# Sheet3.net
KiCad netlist of a schematic drawn in Altium Designer
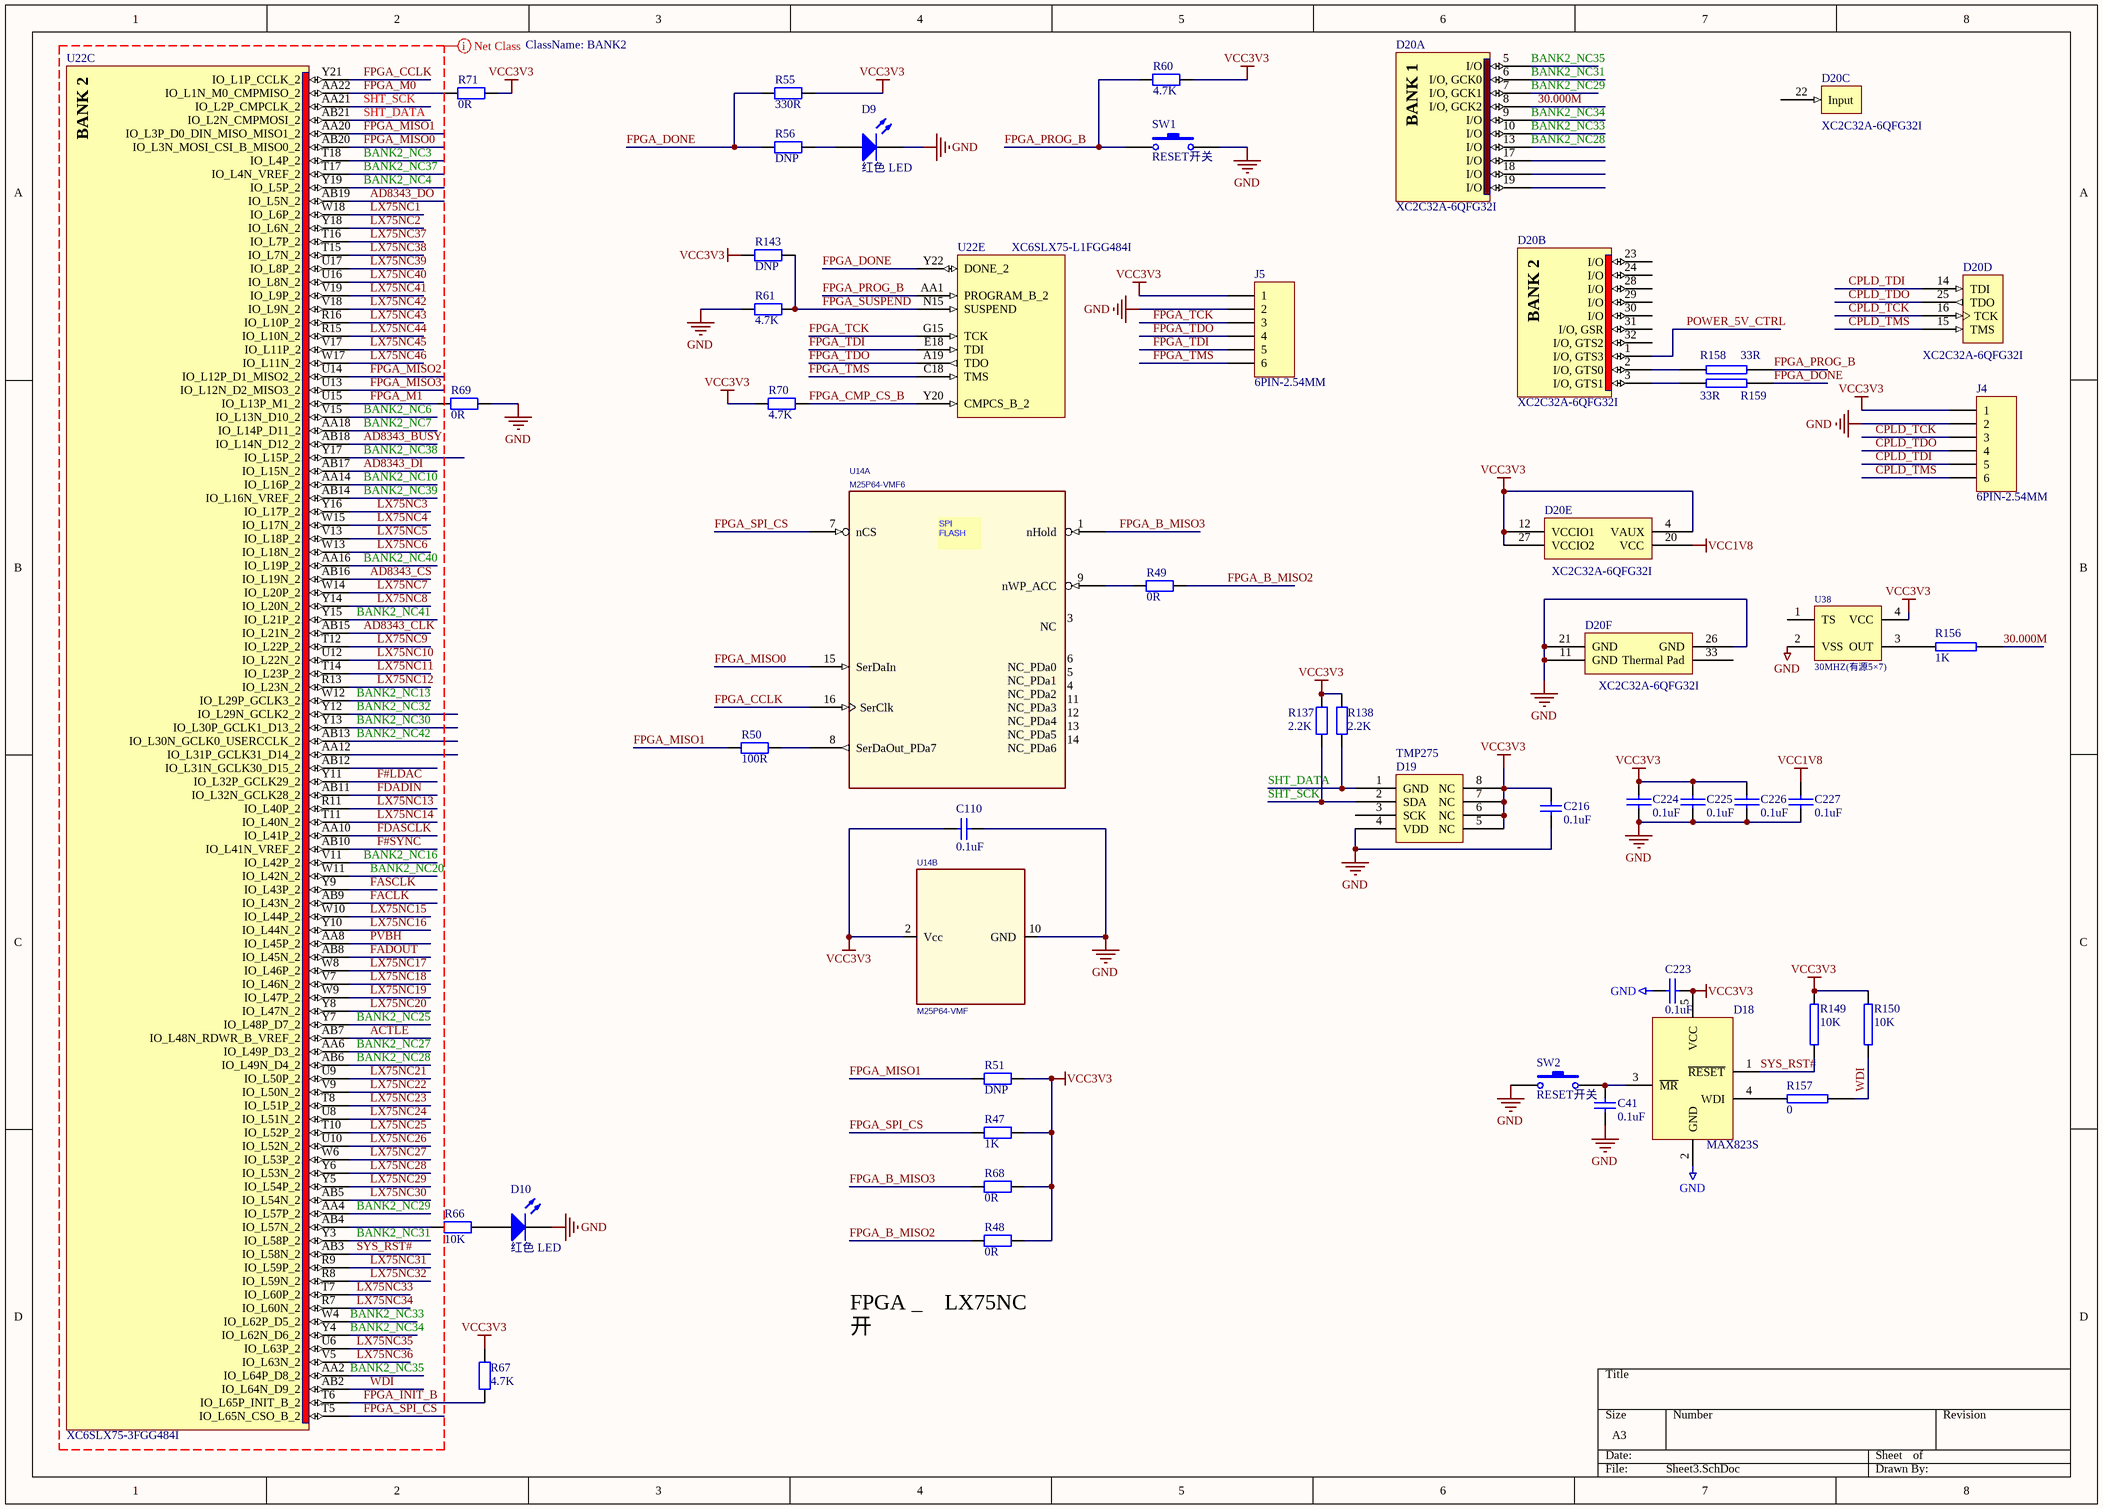
[diagram p0: Sheet3.SchDoc]

(export (version "E")
  (design (tool "Eeschema 10.0.6"))
  (components
    (comp (ref "C41")
      (value "0.1uF")
      (footprint "0603C")
      (description "Capacitor")
      (fields (field (name "PUBLISHER") "Altium Limited"))
      (libsource (lib "Miscellaneous Devices") (part "Cap"))
    )
    (comp (ref "C110")
      (value "0.1uF")
      (footprint "0402C")
      (description "Capacitor")
      (fields (field (name "PUBLISHER") "Altium Limited"))
      (libsource (lib "Miscellaneous Devices") (part "Cap"))
    )
    (comp (ref "C216")
      (value "0.1uF")
      (footprint "0402C")
      (description "Capacitor")
      (fields (field (name "PUBLISHER") "Altium Limited"))
      (libsource (lib "Miscellaneous Devices") (part "Cap"))
    )
    (comp (ref "C223") (value "0.1uF") (footprint "0603X") (libsource (lib "*") (part "2543.S01_104_49")))
    (comp (ref "C224") (value "0.1uF") (footprint "0402C") (libsource (lib "*") (part "2543.S01_104_49")))
    (comp (ref "C225") (value "0.1uF") (footprint "0402C") (libsource (lib "*") (part "2543.S01_104_49")))
    (comp (ref "C226") (value "0.1uF") (footprint "0402C") (libsource (lib "*") (part "2543.S01_104_49")))
    (comp (ref "C227") (value "0.1uF") (footprint "0402C") (libsource (lib "*") (part "2543.S01_104_49")))
    (comp (ref "D9")
      (value "红色 LED")
      (footprint "0805LED")
      (description "Typical RED, GREEN, YELLOW, AMBER GaAs LED")
      (fields (field (name "PUBLISHER") "Altium Limited"))
      (libsource (lib "Miscellaneous Devices") (part "LED2"))
    )
    (comp (ref "D10")
      (value "红色 LED")
      (footprint "0805LED")
      (description "Typical INFRARED GaAs LED")
      (fields (field (name "PUBLISHER") "Altium Limited"))
      (libsource (lib "Miscellaneous Devices") (part "LED0"))
    )
    (comp (ref "D18")
      (value "MAX823S")
      (footprint "MAX823")
      (description "MAX823复位监控芯片")
      (libsource (lib "*") (part "MAX823"))
    )
    (comp (ref "D19") (value "TMP275") (footprint "SMD8XX") (libsource (lib "Schlib1") (part "SHT11")))
    (comp (ref "D20")
      (value "XC2C32A-6QFG32I")
      (footprint "QFG32_N")
      (description "CoolRunner-II 1.8V, 32 Macrocell CPLD, 21 User I/Os, 32-Pin QFNL, Commercial Grade, Pb-Free")
      (fields (field (name "PUBLISHER") "Altium Limited"))
      (libsource (lib "Xilinx CoolRunner II") (part "XC2C32A-6QFG32C"))
    )
    (comp (ref "J4")
      (value "6PIN-2.54MM")
      (footprint "SIP6X")
      (description "Header, 6-Pin")
      (fields (field (name "PUBLISHER") "Altium Limited"))
      (libsource (lib "Miscellaneous Connectors") (part "Header 6"))
    )
    (comp (ref "J5")
      (value "6PIN-2.54MM")
      (footprint "SIP6X")
      (description "Header, 6-Pin")
      (fields (field (name "PUBLISHER") "Altium Limited"))
      (libsource (lib "Miscellaneous Connectors") (part "Header 6"))
    )
    (comp (ref "R47")
      (value "1K")
      (footprint "0603R")
      (description "Resistor")
      (fields (field (name "PUBLISHER") "Altium Limited"))
      (libsource (lib "") (part "Res2_2"))
    )
    (comp (ref "R48")
      (value "0R")
      (footprint "0603R")
      (description "Resistor")
      (fields (field (name "PUBLISHER") "Altium Limited"))
      (libsource (lib "") (part "Res2_2"))
    )
    (comp (ref "R49")
      (value "0R")
      (footprint "0603R")
      (description "Resistor")
      (fields (field (name "PUBLISHER") "Altium Limited"))
      (libsource (lib "") (part "Res2_2"))
    )
    (comp (ref "R50")
      (value "100R")
      (footprint "0603R")
      (description "Resistor")
      (fields (field (name "PUBLISHER") "Altium Limited"))
      (libsource (lib "") (part "Res2_2"))
    )
    (comp (ref "R51")
      (value "DNP")
      (footprint "0603R")
      (description "Resistor")
      (fields (field (name "PUBLISHER") "Altium Limited"))
      (libsource (lib "") (part "Res2_2"))
    )
    (comp (ref "R55")
      (value "330R")
      (footprint "0603R")
      (description "Resistor")
      (fields (field (name "PUBLISHER") "Altium Limited"))
      (libsource (lib "") (part "Res2_2"))
    )
    (comp (ref "R56")
      (value "DNP")
      (footprint "0603R")
      (description "Resistor")
      (fields (field (name "PUBLISHER") "Altium Limited"))
      (libsource (lib "") (part "Res2_2"))
    )
    (comp (ref "R60")
      (value "4.7K")
      (footprint "0603R")
      (description "Resistor")
      (fields (field (name "PUBLISHER") "Altium Limited"))
      (libsource (lib "") (part "Res2_2"))
    )
    (comp (ref "R61")
      (value "4.7K")
      (footprint "0603R")
      (description "Resistor")
      (fields (field (name "PUBLISHER") "Altium Limited"))
      (libsource (lib "") (part "Res2_2"))
    )
    (comp (ref "R66")
      (value "10K")
      (footprint "0603R")
      (description "Resistor")
      (fields (field (name "PUBLISHER") "Altium Limited"))
      (libsource (lib "") (part "Res2_2"))
    )
    (comp (ref "R67")
      (value "4.7K")
      (footprint "0603R")
      (description "Resistor")
      (fields (field (name "PUBLISHER") "Altium Limited"))
      (libsource (lib "") (part "Res2_1"))
    )
    (comp (ref "R68")
      (value "0R")
      (footprint "0603R")
      (description "Resistor")
      (fields (field (name "PUBLISHER") "Altium Limited"))
      (libsource (lib "") (part "Res2_2"))
    )
    (comp (ref "R69")
      (value "0R")
      (footprint "0603R")
      (description "Resistor")
      (fields (field (name "PUBLISHER") "Altium Limited"))
      (libsource (lib "Miscellaneous Devices") (part "Res2"))
    )
    (comp (ref "R70")
      (value "4.7K")
      (footprint "0603R")
      (description "Resistor")
      (fields (field (name "PUBLISHER") "Altium Limited"))
      (libsource (lib "") (part "Res2_2"))
    )
    (comp (ref "R71")
      (value "0R")
      (footprint "0603R")
      (description "Resistor")
      (fields (field (name "PUBLISHER") "Altium Limited"))
      (libsource (lib "Miscellaneous Devices") (part "Res2"))
    )
    (comp (ref "R137")
      (value "2.2K")
      (footprint "0603R")
      (description "Resistor")
      (fields (field (name "PUBLISHER") "Altium Limited"))
      (libsource (lib "Miscellaneous Devices") (part "Res2"))
    )
    (comp (ref "R138")
      (value "2.2K")
      (footprint "0603R")
      (description "Resistor")
      (fields (field (name "PUBLISHER") "Altium Limited"))
      (libsource (lib "Miscellaneous Devices") (part "Res2"))
    )
    (comp (ref "R143")
      (value "DNP")
      (footprint "0603R")
      (description "Resistor")
      (fields (field (name "PUBLISHER") "Altium Limited"))
      (libsource (lib "") (part "Res2_2"))
    )
    (comp (ref "R149")
      (value "10K")
      (footprint "0603X")
      (description "电阻")
      (libsource (lib "") (part "RES2_1"))
    )
    (comp (ref "R150")
      (value "10K")
      (footprint "0603X")
      (description "电阻")
      (libsource (lib "") (part "RES2_1"))
    )
    (comp (ref "R156") (value "1K") (footprint "0603") (libsource (lib "*") (part "RES2")))
    (comp (ref "R157") (value "0") (footprint "0603") (libsource (lib "*") (part "RES2")))
    (comp (ref "R158") (value "33R") (footprint "0603R") (libsource (lib "*") (part "RES2")))
    (comp (ref "R159") (value "33R") (footprint "0603R") (libsource (lib "*") (part "RES2")))
    (comp (ref "SW1")
      (value "RESET开关")
      (footprint "RESETKEY")
      (description "Switch")
      (fields (field (name "PUBLISHER") "Altium Limited"))
      (libsource (lib "Miscellaneous Devices") (part "SW-PB"))
    )
    (comp (ref "SW2")
      (value "RESET开关")
      (footprint "RESETKEY")
      (description "Switch")
      (fields (field (name "PUBLISHER") "Altium Limited"))
      (libsource (lib "Miscellaneous Devices") (part "SW-PB"))
    )
    (comp (ref "U14")
      (value "M25P64-VMF")
      (footprint "SOIC16")
      (description "SPI FLASH 128Mbit, 104MHz, 64kB sector")
      (fields (field (name "FULL PART NO") "S25FL128P0XMFI00") (field (name "MANUFACTURER") "Spansion"))
      (libsource (lib "") (part "SPI FLASH 128Mb S25FL128P_1"))
    )
    (comp (ref "U22")
      (value "XC6SLX75-3FGG484I")
      (footprint "FGG484")
      (fields (field (name "PUBLISHER") "Altium Limited"))
      (libsource (lib "Xilinx Spartan-6") (part "XC6SLX45-L1FGG484I"))
    )
    (comp (ref "U38") (value "30MHZ(有源5×7)") (footprint "30M") (libsource (lib "*") (part "CRYSTAL")))
  )
  (nets
    (net (code "1") (name "/30.000M") (class "Default")
      (node (ref "D20") (pin "8") (pinfunction "I/O,_GCK2_8") (pintype "bidirectional"))
      (node (ref "R156") (pin "2") (pinfunction "2_2") (pintype "passive"))
    )
    (net (code "2") (name "/ACTLE") (class "Default")
      (node (ref "U22") (pin "AB7") (pinfunction "IO_L48N_RDWR_B_VREF_2_AB7") (pintype "bidirectional"))
    )
    (net (code "3") (name "/AD8343_BUSY") (class "Default")
      (node (ref "U22") (pin "AB18") (pinfunction "IO_L14N_D12_2_AB18") (pintype "bidirectional"))
    )
    (net (code "4") (name "/AD8343_CLK") (class "Default")
      (node (ref "U22") (pin "AB15") (pinfunction "IO_L21N_2_AB15") (pintype "bidirectional"))
    )
    (net (code "5") (name "/AD8343_CS") (class "Default")
      (node (ref "U22") (pin "AB16") (pinfunction "IO_L19N_2_AB16") (pintype "bidirectional"))
    )
    (net (code "6") (name "/AD8343_DI") (class "Default")
      (node (ref "U22") (pin "AB17") (pinfunction "IO_L15N_2_AB17") (pintype "bidirectional"))
    )
    (net (code "7") (name "/AD8343_DO") (class "Default")
      (node (ref "U22") (pin "AB19") (pinfunction "IO_L5N_2_AB19") (pintype "bidirectional"))
    )
    (net (code "8") (name "/BANK2_NC3") (class "Default")
      (node (ref "U22") (pin "T18") (pinfunction "IO_L4P_2_T18") (pintype "bidirectional"))
    )
    (net (code "9") (name "/BANK2_NC4") (class "Default")
      (node (ref "U22") (pin "Y19") (pinfunction "IO_L5P_2_Y19") (pintype "bidirectional"))
    )
    (net (code "10") (name "/BANK2_NC6") (class "Default")
      (node (ref "U22") (pin "V15") (pinfunction "IO_L13N_D10_2_V15") (pintype "bidirectional"))
    )
    (net (code "11") (name "/BANK2_NC7") (class "Default")
      (node (ref "U22") (pin "AA18") (pinfunction "IO_L14P_D11_2_AA18") (pintype "bidirectional"))
    )
    (net (code "12") (name "/BANK2_NC10") (class "Default")
      (node (ref "U22") (pin "AA14") (pinfunction "IO_L16P_2_AA14") (pintype "bidirectional"))
    )
    (net (code "13") (name "/BANK2_NC13") (class "Default")
      (node (ref "U22") (pin "W12") (pinfunction "IO_L29P_GCLK3_2_W12") (pintype "bidirectional"))
    )
    (net (code "14") (name "/BANK2_NC16") (class "Default")
      (node (ref "U22") (pin "V11") (pinfunction "IO_L42P_2_V11") (pintype "bidirectional"))
    )
    (net (code "15") (name "/BANK2_NC20") (class "Default")
      (node (ref "U22") (pin "W11") (pinfunction "IO_L42N_2_W11") (pintype "bidirectional"))
    )
    (net (code "16") (name "/BANK2_NC25") (class "Default")
      (node (ref "U22") (pin "Y7") (pinfunction "IO_L48P_D7_2_Y7") (pintype "bidirectional"))
    )
    (net (code "17") (name "/BANK2_NC27") (class "Default")
      (node (ref "U22") (pin "AA6") (pinfunction "IO_L49P_D3_2_AA6") (pintype "bidirectional"))
    )
    (net (code "18") (name "/BANK2_NC28") (class "Default")
      (node (ref "D20") (pin "13") (pinfunction "I/O_13") (pintype "bidirectional"))
      (node (ref "U22") (pin "AB6") (pinfunction "IO_L49N_D4_2_AB6") (pintype "bidirectional"))
    )
    (net (code "19") (name "/BANK2_NC29") (class "Default")
      (node (ref "D20") (pin "7") (pinfunction "I/O,_GCK1_7") (pintype "bidirectional"))
      (node (ref "U22") (pin "AA4") (pinfunction "IO_L57P_2_AA4") (pintype "bidirectional"))
    )
    (net (code "20") (name "/BANK2_NC30") (class "Default")
      (node (ref "U22") (pin "Y13") (pinfunction "IO_L30P_GCLK1_D13_2_Y13") (pintype "bidirectional"))
    )
    (net (code "21") (name "/BANK2_NC31") (class "Default")
      (node (ref "D20") (pin "6") (pinfunction "I/O,_GCK0_6") (pintype "bidirectional"))
      (node (ref "U22") (pin "Y3") (pinfunction "IO_L58P_2_Y3") (pintype "bidirectional"))
    )
    (net (code "22") (name "/BANK2_NC32") (class "Default")
      (node (ref "U22") (pin "Y12") (pinfunction "IO_L29N_GCLK2_2_Y12") (pintype "bidirectional"))
    )
    (net (code "23") (name "/BANK2_NC33") (class "Default")
      (node (ref "D20") (pin "10") (pinfunction "I/O_10") (pintype "bidirectional"))
      (node (ref "U22") (pin "W4") (pinfunction "IO_L62P_D5_2_W4") (pintype "bidirectional"))
    )
    (net (code "24") (name "/BANK2_NC34") (class "Default")
      (node (ref "D20") (pin "9") (pinfunction "I/O_9") (pintype "bidirectional"))
      (node (ref "U22") (pin "Y4") (pinfunction "IO_L62N_D6_2_Y4") (pintype "bidirectional"))
    )
    (net (code "25") (name "/BANK2_NC35") (class "Default")
      (node (ref "D20") (pin "5") (pinfunction "I/O_5") (pintype "bidirectional"))
      (node (ref "U22") (pin "AA2") (pinfunction "IO_L64P_D8_2_AA2") (pintype "bidirectional"))
    )
    (net (code "26") (name "/BANK2_NC37") (class "Default")
      (node (ref "U22") (pin "T17") (pinfunction "IO_L4N_VREF_2_T17") (pintype "bidirectional"))
    )
    (net (code "27") (name "/BANK2_NC38") (class "Default")
      (node (ref "U22") (pin "Y17") (pinfunction "IO_L15P_2_Y17") (pintype "bidirectional"))
    )
    (net (code "28") (name "/BANK2_NC39") (class "Default")
      (node (ref "U22") (pin "AB14") (pinfunction "IO_L16N_VREF_2_AB14") (pintype "bidirectional"))
    )
    (net (code "29") (name "/BANK2_NC40") (class "Default")
      (node (ref "U22") (pin "AA16") (pinfunction "IO_L19P_2_AA16") (pintype "bidirectional"))
    )
    (net (code "30") (name "/BANK2_NC41") (class "Default")
      (node (ref "U22") (pin "Y15") (pinfunction "IO_L21P_2_Y15") (pintype "bidirectional"))
    )
    (net (code "31") (name "/BANK2_NC42") (class "Default")
      (node (ref "U22") (pin "AB13") (pinfunction "IO_L30N_GCLK0_USERCCLK_2_AB13") (pintype "bidirectional"))
    )
    (net (code "32") (name "/CPLD_TCK") (class "Default")
      (node (ref "D20") (pin "16") (pinfunction "TCK_16") (pintype "input"))
      (node (ref "J4") (pin "3") (pinfunction "3_3") (pintype "passive"))
    )
    (net (code "33") (name "/CPLD_TDI") (class "Default")
      (node (ref "D20") (pin "14") (pinfunction "TDI_14") (pintype "input"))
      (node (ref "J4") (pin "5") (pinfunction "5_5") (pintype "passive"))
    )
    (net (code "34") (name "/CPLD_TDO") (class "Default")
      (node (ref "D20") (pin "25") (pinfunction "TDO_25") (pintype "output"))
      (node (ref "J4") (pin "4") (pinfunction "4_4") (pintype "passive"))
    )
    (net (code "35") (name "/CPLD_TMS") (class "Default")
      (node (ref "D20") (pin "15") (pinfunction "TMS_15") (pintype "input"))
      (node (ref "J4") (pin "6") (pinfunction "6_6") (pintype "passive"))
    )
    (net (code "36") (name "/F#LDAC") (class "Default")
      (node (ref "U22") (pin "Y11") (pinfunction "IO_L32P_GCLK29_2_Y11") (pintype "bidirectional"))
    )
    (net (code "37") (name "/F#SYNC") (class "Default")
      (node (ref "U22") (pin "AB10") (pinfunction "IO_L41N_VREF_2_AB10") (pintype "bidirectional"))
    )
    (net (code "38") (name "/FACLK") (class "Default")
      (node (ref "U22") (pin "AB9") (pinfunction "IO_L43N_2_AB9") (pintype "bidirectional"))
    )
    (net (code "39") (name "/FADOUT") (class "Default")
      (node (ref "U22") (pin "AB8") (pinfunction "IO_L45N_2_AB8") (pintype "bidirectional"))
    )
    (net (code "40") (name "/FASCLK") (class "Default")
      (node (ref "U22") (pin "Y9") (pinfunction "IO_L43P_2_Y9") (pintype "bidirectional"))
    )
    (net (code "41") (name "/FDADIN") (class "Default")
      (node (ref "U22") (pin "AB11") (pinfunction "IO_L32N_GCLK28_2_AB11") (pintype "bidirectional"))
    )
    (net (code "42") (name "/FDASCLK") (class "Default")
      (node (ref "U22") (pin "AA10") (pinfunction "IO_L41P_2_AA10") (pintype "bidirectional"))
    )
    (net (code "43") (name "/FPGA_B_MISO2") (class "Default")
      (node (ref "R48") (pin "1") (pinfunction "1_1") (pintype "passive"))
      (node (ref "R49") (pin "2") (pinfunction "2_2") (pintype "passive"))
    )
    (net (code "44") (name "/FPGA_B_MISO3") (class "Default")
      (node (ref "R68") (pin "1") (pinfunction "1_1") (pintype "passive"))
      (node (ref "U14") (pin "1") (pinfunction "nHold_1") (pintype "input"))
    )
    (net (code "45") (name "/FPGA_CCLK") (class "Default")
      (node (ref "U14") (pin "16") (pinfunction "SerClk_16") (pintype "input"))
      (node (ref "U22") (pin "Y21") (pinfunction "IO_L1P_CCLK_2_Y21") (pintype "bidirectional"))
    )
    (net (code "46") (name "/FPGA_CMP_CS_B") (class "Default")
      (node (ref "R70") (pin "2") (pinfunction "2_2") (pintype "passive"))
      (node (ref "U22") (pin "Y20") (pinfunction "CMPCS_B_2_Y20") (pintype "input"))
    )
    (net (code "47") (name "/FPGA_DONE") (class "Default")
      (node (ref "R159") (pin "2") (pinfunction "2_2") (pintype "passive"))
      (node (ref "R55") (pin "1") (pinfunction "1_1") (pintype "passive"))
      (node (ref "R56") (pin "1") (pinfunction "1_1") (pintype "passive"))
      (node (ref "U22") (pin "Y22") (pinfunction "DONE_2_Y22") (pintype "bidirectional"))
    )
    (net (code "48") (name "/FPGA_INIT_B") (class "Default")
      (node (ref "R67") (pin "2") (pinfunction "2_2") (pintype "passive"))
      (node (ref "U22") (pin "T6") (pinfunction "IO_L65P_INIT_B_2_T6") (pintype "bidirectional"))
    )
    (net (code "49") (name "/FPGA_M0") (class "Default")
      (node (ref "R71") (pin "2") (pinfunction "2_2") (pintype "passive"))
      (node (ref "U22") (pin "AA22") (pinfunction "IO_L1N_M0_CMPMISO_2_AA22") (pintype "bidirectional"))
    )
    (net (code "50") (name "/FPGA_M1") (class "Default")
      (node (ref "R69") (pin "2") (pinfunction "2_2") (pintype "passive"))
      (node (ref "U22") (pin "U15") (pinfunction "IO_L13P_M1_2_U15") (pintype "bidirectional"))
    )
    (net (code "51") (name "/FPGA_MISO0") (class "Default")
      (node (ref "U14") (pin "15") (pinfunction "SerDaIn_15") (pintype "input"))
      (node (ref "U22") (pin "AB20") (pinfunction "IO_L3N_MOSI_CSI_B_MISO0_2_AB20") (pintype "bidirectional"))
    )
    (net (code "52") (name "/FPGA_MISO1") (class "Default")
      (node (ref "R50") (pin "1") (pinfunction "1_1") (pintype "passive"))
      (node (ref "R51") (pin "1") (pinfunction "1_1") (pintype "passive"))
      (node (ref "U22") (pin "AA20") (pinfunction "IO_L3P_D0_DIN_MISO_MISO1_2_AA20") (pintype "bidirectional"))
    )
    (net (code "53") (name "/FPGA_MISO2") (class "Default")
      (node (ref "U22") (pin "U14") (pinfunction "IO_L12P_D1_MISO2_2_U14") (pintype "bidirectional"))
    )
    (net (code "54") (name "/FPGA_MISO3") (class "Default")
      (node (ref "U22") (pin "U13") (pinfunction "IO_L12N_D2_MISO3_2_U13") (pintype "bidirectional"))
    )
    (net (code "55") (name "/FPGA_PROG_B") (class "Default")
      (node (ref "R158") (pin "2") (pinfunction "2_2") (pintype "passive"))
      (node (ref "R60") (pin "1") (pinfunction "1_1") (pintype "passive"))
      (node (ref "SW1") (pin "1") (pinfunction "1_1") (pintype "passive"))
      (node (ref "U22") (pin "AA1") (pinfunction "PROGRAM_B_2_AA1") (pintype "input"))
    )
    (net (code "56") (name "/FPGA_SPI_CS") (class "Default")
      (node (ref "R47") (pin "1") (pinfunction "1_1") (pintype "passive"))
      (node (ref "U14") (pin "7") (pinfunction "nCS_7") (pintype "input"))
      (node (ref "U22") (pin "T5") (pinfunction "IO_L65N_CSO_B_2_T5") (pintype "bidirectional"))
    )
    (net (code "57") (name "/FPGA_SUSPEND") (class "Default")
      (node (ref "R143") (pin "2") (pinfunction "2_2") (pintype "passive"))
      (node (ref "R61") (pin "2") (pinfunction "2_2") (pintype "passive"))
      (node (ref "U22") (pin "N15") (pinfunction "SUSPEND_N15") (pintype "input"))
    )
    (net (code "58") (name "/FPGA_TCK") (class "Default")
      (node (ref "J5") (pin "3") (pinfunction "3_3") (pintype "passive"))
      (node (ref "U22") (pin "G15") (pinfunction "TCK_G15") (pintype "input"))
    )
    (net (code "59") (name "/FPGA_TDI") (class "Default")
      (node (ref "J5") (pin "5") (pinfunction "5_5") (pintype "passive"))
      (node (ref "U22") (pin "E18") (pinfunction "TDI_E18") (pintype "input"))
    )
    (net (code "60") (name "/FPGA_TDO") (class "Default")
      (node (ref "J5") (pin "4") (pinfunction "4_4") (pintype "passive"))
      (node (ref "U22") (pin "A19") (pinfunction "TDO_A19") (pintype "output"))
    )
    (net (code "61") (name "/FPGA_TMS") (class "Default")
      (node (ref "J5") (pin "6") (pinfunction "6_6") (pintype "passive"))
      (node (ref "U22") (pin "C18") (pinfunction "TMS_C18") (pintype "input"))
    )
    (net (code "62") (name "/LX75NC1") (class "Default")
      (node (ref "U22") (pin "W18") (pinfunction "IO_L6P_2_W18") (pintype "bidirectional"))
    )
    (net (code "63") (name "/LX75NC2") (class "Default")
      (node (ref "U22") (pin "Y18") (pinfunction "IO_L6N_2_Y18") (pintype "bidirectional"))
    )
    (net (code "64") (name "/LX75NC3") (class "Default")
      (node (ref "U22") (pin "Y16") (pinfunction "IO_L17P_2_Y16") (pintype "bidirectional"))
    )
    (net (code "65") (name "/LX75NC4") (class "Default")
      (node (ref "U22") (pin "W15") (pinfunction "IO_L17N_2_W15") (pintype "bidirectional"))
    )
    (net (code "66") (name "/LX75NC5") (class "Default")
      (node (ref "U22") (pin "V13") (pinfunction "IO_L18P_2_V13") (pintype "bidirectional"))
    )
    (net (code "67") (name "/LX75NC6") (class "Default")
      (node (ref "U22") (pin "W13") (pinfunction "IO_L18N_2_W13") (pintype "bidirectional"))
    )
    (net (code "68") (name "/LX75NC7") (class "Default")
      (node (ref "U22") (pin "W14") (pinfunction "IO_L20P_2_W14") (pintype "bidirectional"))
    )
    (net (code "69") (name "/LX75NC8") (class "Default")
      (node (ref "U22") (pin "Y14") (pinfunction "IO_L20N_2_Y14") (pintype "bidirectional"))
    )
    (net (code "70") (name "/LX75NC9") (class "Default")
      (node (ref "U22") (pin "T12") (pinfunction "IO_L22P_2_T12") (pintype "bidirectional"))
    )
    (net (code "71") (name "/LX75NC10") (class "Default")
      (node (ref "U22") (pin "U12") (pinfunction "IO_L22N_2_U12") (pintype "bidirectional"))
    )
    (net (code "72") (name "/LX75NC11") (class "Default")
      (node (ref "U22") (pin "T14") (pinfunction "IO_L23P_2_T14") (pintype "bidirectional"))
    )
    (net (code "73") (name "/LX75NC12") (class "Default")
      (node (ref "U22") (pin "R13") (pinfunction "IO_L23N_2_R13") (pintype "bidirectional"))
    )
    (net (code "74") (name "/LX75NC13") (class "Default")
      (node (ref "U22") (pin "R11") (pinfunction "IO_L40P_2_R11") (pintype "bidirectional"))
    )
    (net (code "75") (name "/LX75NC14") (class "Default")
      (node (ref "U22") (pin "T11") (pinfunction "IO_L40N_2_T11") (pintype "bidirectional"))
    )
    (net (code "76") (name "/LX75NC15") (class "Default")
      (node (ref "U22") (pin "W10") (pinfunction "IO_L44P_2_W10") (pintype "bidirectional"))
    )
    (net (code "77") (name "/LX75NC16") (class "Default")
      (node (ref "U22") (pin "Y10") (pinfunction "IO_L44N_2_Y10") (pintype "bidirectional"))
    )
    (net (code "78") (name "/LX75NC17") (class "Default")
      (node (ref "U22") (pin "W8") (pinfunction "IO_L46P_2_W8") (pintype "bidirectional"))
    )
    (net (code "79") (name "/LX75NC18") (class "Default")
      (node (ref "U22") (pin "V7") (pinfunction "IO_L46N_2_V7") (pintype "bidirectional"))
    )
    (net (code "80") (name "/LX75NC19") (class "Default")
      (node (ref "U22") (pin "W9") (pinfunction "IO_L47P_2_W9") (pintype "bidirectional"))
    )
    (net (code "81") (name "/LX75NC20") (class "Default")
      (node (ref "U22") (pin "Y8") (pinfunction "IO_L47N_2_Y8") (pintype "bidirectional"))
    )
    (net (code "82") (name "/LX75NC21") (class "Default")
      (node (ref "U22") (pin "U9") (pinfunction "IO_L50P_2_U9") (pintype "bidirectional"))
    )
    (net (code "83") (name "/LX75NC22") (class "Default")
      (node (ref "U22") (pin "V9") (pinfunction "IO_L50N_2_V9") (pintype "bidirectional"))
    )
    (net (code "84") (name "/LX75NC23") (class "Default")
      (node (ref "U22") (pin "T8") (pinfunction "IO_L51P_2_T8") (pintype "bidirectional"))
    )
    (net (code "85") (name "/LX75NC24") (class "Default")
      (node (ref "U22") (pin "U8") (pinfunction "IO_L51N_2_U8") (pintype "bidirectional"))
    )
    (net (code "86") (name "/LX75NC25") (class "Default")
      (node (ref "U22") (pin "T10") (pinfunction "IO_L52P_2_T10") (pintype "bidirectional"))
    )
    (net (code "87") (name "/LX75NC26") (class "Default")
      (node (ref "U22") (pin "U10") (pinfunction "IO_L52N_2_U10") (pintype "bidirectional"))
    )
    (net (code "88") (name "/LX75NC27") (class "Default")
      (node (ref "U22") (pin "W6") (pinfunction "IO_L53P_2_W6") (pintype "bidirectional"))
    )
    (net (code "89") (name "/LX75NC28") (class "Default")
      (node (ref "U22") (pin "Y6") (pinfunction "IO_L53N_2_Y6") (pintype "bidirectional"))
    )
    (net (code "90") (name "/LX75NC29") (class "Default")
      (node (ref "U22") (pin "Y5") (pinfunction "IO_L54P_2_Y5") (pintype "bidirectional"))
    )
    (net (code "91") (name "/LX75NC30") (class "Default")
      (node (ref "U22") (pin "AB5") (pinfunction "IO_L54N_2_AB5") (pintype "bidirectional"))
    )
    (net (code "92") (name "/LX75NC31") (class "Default")
      (node (ref "U22") (pin "R9") (pinfunction "IO_L59P_2_R9") (pintype "bidirectional"))
    )
    (net (code "93") (name "/LX75NC32") (class "Default")
      (node (ref "U22") (pin "R8") (pinfunction "IO_L59N_2_R8") (pintype "bidirectional"))
    )
    (net (code "94") (name "/LX75NC33") (class "Default")
      (node (ref "U22") (pin "T7") (pinfunction "IO_L60P_2_T7") (pintype "bidirectional"))
    )
    (net (code "95") (name "/LX75NC34") (class "Default")
      (node (ref "U22") (pin "R7") (pinfunction "IO_L60N_2_R7") (pintype "bidirectional"))
    )
    (net (code "96") (name "/LX75NC35") (class "Default")
      (node (ref "U22") (pin "U6") (pinfunction "IO_L63P_2_U6") (pintype "bidirectional"))
    )
    (net (code "97") (name "/LX75NC36") (class "Default")
      (node (ref "U22") (pin "V5") (pinfunction "IO_L63N_2_V5") (pintype "bidirectional"))
    )
    (net (code "98") (name "/LX75NC37") (class "Default")
      (node (ref "U22") (pin "T16") (pinfunction "IO_L7P_2_T16") (pintype "bidirectional"))
    )
    (net (code "99") (name "/LX75NC38") (class "Default")
      (node (ref "U22") (pin "T15") (pinfunction "IO_L7N_2_T15") (pintype "bidirectional"))
    )
    (net (code "100") (name "/LX75NC39") (class "Default")
      (node (ref "U22") (pin "U17") (pinfunction "IO_L8P_2_U17") (pintype "bidirectional"))
    )
    (net (code "101") (name "/LX75NC40") (class "Default")
      (node (ref "U22") (pin "U16") (pinfunction "IO_L8N_2_U16") (pintype "bidirectional"))
    )
    (net (code "102") (name "/LX75NC41") (class "Default")
      (node (ref "U22") (pin "V19") (pinfunction "IO_L9P_2_V19") (pintype "bidirectional"))
    )
    (net (code "103") (name "/LX75NC42") (class "Default")
      (node (ref "U22") (pin "V18") (pinfunction "IO_L9N_2_V18") (pintype "bidirectional"))
    )
    (net (code "104") (name "/LX75NC43") (class "Default")
      (node (ref "U22") (pin "R16") (pinfunction "IO_L10P_2_R16") (pintype "bidirectional"))
    )
    (net (code "105") (name "/LX75NC44") (class "Default")
      (node (ref "U22") (pin "R15") (pinfunction "IO_L10N_2_R15") (pintype "bidirectional"))
    )
    (net (code "106") (name "/LX75NC45") (class "Default")
      (node (ref "U22") (pin "V17") (pinfunction "IO_L11P_2_V17") (pintype "bidirectional"))
    )
    (net (code "107") (name "/LX75NC46") (class "Default")
      (node (ref "U22") (pin "W17") (pinfunction "IO_L11N_2_W17") (pintype "bidirectional"))
    )
    (net (code "108") (name "/POWER_5V_CTRL") (class "Default")
      (node (ref "D20") (pin "1") (pinfunction "I/O,_GTS3_1") (pintype "bidirectional"))
    )
    (net (code "109") (name "/PVBH") (class "Default")
      (node (ref "U22") (pin "AA8") (pinfunction "IO_L45P_2_AA8") (pintype "bidirectional"))
    )
    (net (code "110") (name "/SHT_DATA") (class "Default")
      (node (ref "D19") (pin "1") (pinfunction "GND_1") (pintype "passive"))
      (node (ref "R138") (pin "2") (pinfunction "2_2") (pintype "passive"))
      (node (ref "U22") (pin "AB21") (pinfunction "IO_L2N_CMPMOSI_2_AB21") (pintype "bidirectional"))
    )
    (net (code "111") (name "/SHT_SCK") (class "Default")
      (node (ref "D19") (pin "2") (pinfunction "SDA_2") (pintype "passive"))
      (node (ref "R137") (pin "2") (pinfunction "2_2") (pintype "passive"))
      (node (ref "U22") (pin "AA21") (pinfunction "IO_L2P_CMPCLK_2_AA21") (pintype "bidirectional"))
    )
    (net (code "112") (name "/SYS_RST#") (class "Default")
      (node (ref "D18") (pin "1") (pinfunction "~{RESET}_1") (pintype "passive"))
      (node (ref "R149") (pin "1") (pinfunction "1_1") (pintype "passive"))
      (node (ref "U22") (pin "AB3") (pinfunction "IO_L58N_2_AB3") (pintype "bidirectional"))
    )
    (net (code "113") (name "/WDI") (class "Default")
      (node (ref "R150") (pin "1") (pinfunction "1_1") (pintype "passive"))
      (node (ref "R157") (pin "2") (pinfunction "2_2") (pintype "passive"))
      (node (ref "U22") (pin "AB2") (pinfunction "IO_L64N_D9_2_AB2") (pintype "bidirectional"))
    )
    (net (code "114") (name "GND") (class "Default")
      (node (ref "C110") (pin "1") (pinfunction "1_1") (pintype "passive"))
      (node (ref "C216") (pin "1") (pinfunction "1_1") (pintype "passive"))
      (node (ref "C223") (pin "1") (pintype "passive"))
      (node (ref "C224") (pin "1") (pintype "passive"))
      (node (ref "C225") (pin "1") (pintype "passive"))
      (node (ref "C226") (pin "1") (pintype "passive"))
      (node (ref "C227") (pin "1") (pintype "passive"))
      (node (ref "C41") (pin "1") (pinfunction "1_1") (pintype "passive"))
      (node (ref "D10") (pin "2") (pinfunction "K_2") (pintype "passive"))
      (node (ref "D18") (pin "2") (pinfunction "GND_2") (pintype "passive"))
      (node (ref "D19") (pin "4") (pinfunction "VDD_4") (pintype "passive"))
      (node (ref "D20") (pin "11") (pinfunction "GND_11") (pintype "power_in"))
      (node (ref "D20") (pin "21") (pinfunction "GND_21") (pintype "power_in"))
      (node (ref "D20") (pin "26") (pinfunction "GND_26") (pintype "power_in"))
      (node (ref "D9") (pin "2") (pinfunction "K_2") (pintype "passive"))
      (node (ref "J4") (pin "2") (pinfunction "2_2") (pintype "passive"))
      (node (ref "J5") (pin "2") (pinfunction "2_2") (pintype "passive"))
      (node (ref "R61") (pin "1") (pinfunction "1_1") (pintype "passive"))
      (node (ref "R69") (pin "1") (pinfunction "1_1") (pintype "passive"))
      (node (ref "SW1") (pin "2") (pinfunction "2_2") (pintype "passive"))
      (node (ref "SW2") (pin "1") (pinfunction "1_1") (pintype "passive"))
      (node (ref "U14") (pin "10") (pinfunction "GND_10") (pintype "power_in"))
      (node (ref "U38") (pin "2") (pinfunction "VSS_2") (pintype "passive"))
    )
    (net (code "115") (name "Net-(D9-A)") (class "Default")
      (node (ref "D9") (pin "1") (pinfunction "A_1") (pintype "passive"))
      (node (ref "R56") (pin "2") (pinfunction "2_2") (pintype "passive"))
    )
    (net (code "116") (name "Net-(D10-A)") (class "Default")
      (node (ref "D10") (pin "1") (pinfunction "A_1") (pintype "passive"))
      (node (ref "R66") (pin "2") (pinfunction "2_2") (pintype "passive"))
    )
    (net (code "117") (name "Net-(D18-WDI)") (class "Default")
      (node (ref "D18") (pin "4") (pinfunction "WDI_4") (pintype "passive"))
      (node (ref "R157") (pin "1") (pinfunction "1_1") (pintype "passive"))
    )
    (net (code "118") (name "Net-(D18-~{MR})") (class "Default")
      (node (ref "C41") (pin "2") (pinfunction "2_2") (pintype "passive"))
      (node (ref "D18") (pin "3") (pinfunction "~{MR}_3") (pintype "passive"))
      (node (ref "SW2") (pin "2") (pinfunction "2_2") (pintype "passive"))
    )
    (net (code "119") (name "Net-(D20B-I{slash}O,_GTS0)") (class "Default")
      (node (ref "D20") (pin "2") (pinfunction "I/O,_GTS0_2") (pintype "bidirectional"))
      (node (ref "R158") (pin "1") (pinfunction "1_1") (pintype "passive"))
    )
    (net (code "120") (name "Net-(D20B-I{slash}O,_GTS1)") (class "Default")
      (node (ref "D20") (pin "3") (pinfunction "I/O,_GTS1_3") (pintype "bidirectional"))
      (node (ref "R159") (pin "1") (pinfunction "1_1") (pintype "passive"))
    )
    (net (code "121") (name "Net-(U14A-SerDaOut_PDa7)") (class "Default")
      (node (ref "R50") (pin "2") (pinfunction "2_2") (pintype "passive"))
      (node (ref "U14") (pin "8") (pinfunction "SerDaOut_PDa7_8") (pintype "output"))
    )
    (net (code "122") (name "Net-(U14A-nWP_ACC)") (class "Default")
      (node (ref "R49") (pin "1") (pinfunction "1_1") (pintype "passive"))
      (node (ref "U14") (pin "9") (pinfunction "nWP_ACC_9") (pintype "input"))
    )
    (net (code "123") (name "Net-(U22C-IO_L57N_2)") (class "Default")
      (node (ref "R66") (pin "1") (pinfunction "1_1") (pintype "passive"))
      (node (ref "U22") (pin "AB4") (pinfunction "IO_L57N_2_AB4") (pintype "bidirectional"))
    )
    (net (code "124") (name "Net-(U38-OUT)") (class "Default")
      (node (ref "R156") (pin "1") (pinfunction "1_1") (pintype "passive"))
      (node (ref "U38") (pin "3") (pinfunction "OUT_3") (pintype "passive"))
    )
    (net (code "125") (name "VCC1V8") (class "Default")
      (node (ref "C227") (pin "2") (pintype "passive"))
      (node (ref "D20") (pin "20") (pinfunction "VCC_20") (pintype "power_in"))
    )
    (net (code "126") (name "VCC3V3") (class "Default")
      (node (ref "C110") (pin "2") (pinfunction "2_2") (pintype "passive"))
      (node (ref "C216") (pin "2") (pinfunction "2_2") (pintype "passive"))
      (node (ref "C223") (pin "2") (pintype "passive"))
      (node (ref "C224") (pin "2") (pintype "passive"))
      (node (ref "C225") (pin "2") (pintype "passive"))
      (node (ref "C226") (pin "2") (pintype "passive"))
      (node (ref "D18") (pin "5") (pinfunction "VCC_5") (pintype "passive"))
      (node (ref "D19") (pin "5") (pinfunction "NC_5") (pintype "passive"))
      (node (ref "D19") (pin "6") (pinfunction "NC_6") (pintype "passive"))
      (node (ref "D19") (pin "7") (pinfunction "NC_7") (pintype "passive"))
      (node (ref "D19") (pin "8") (pinfunction "NC_8") (pintype "passive"))
      (node (ref "D20") (pin "12") (pinfunction "VCCIO1_12") (pintype "power_in"))
      (node (ref "D20") (pin "27") (pinfunction "VCCIO2_27") (pintype "power_in"))
      (node (ref "D20") (pin "4") (pinfunction "VAUX_4") (pintype "power_in"))
      (node (ref "J4") (pin "1") (pinfunction "1_1") (pintype "passive"))
      (node (ref "J5") (pin "1") (pinfunction "1_1") (pintype "passive"))
      (node (ref "R137") (pin "1") (pinfunction "1_1") (pintype "passive"))
      (node (ref "R138") (pin "1") (pinfunction "1_1") (pintype "passive"))
      (node (ref "R143") (pin "1") (pinfunction "1_1") (pintype "passive"))
      (node (ref "R149") (pin "2") (pinfunction "2_2") (pintype "passive"))
      (node (ref "R150") (pin "2") (pinfunction "2_2") (pintype "passive"))
      (node (ref "R47") (pin "2") (pinfunction "2_2") (pintype "passive"))
      (node (ref "R48") (pin "2") (pinfunction "2_2") (pintype "passive"))
      (node (ref "R51") (pin "2") (pinfunction "2_2") (pintype "passive"))
      (node (ref "R55") (pin "2") (pinfunction "2_2") (pintype "passive"))
      (node (ref "R60") (pin "2") (pinfunction "2_2") (pintype "passive"))
      (node (ref "R67") (pin "1") (pinfunction "1_1") (pintype "passive"))
      (node (ref "R68") (pin "2") (pinfunction "2_2") (pintype "passive"))
      (node (ref "R70") (pin "1") (pinfunction "1_1") (pintype "passive"))
      (node (ref "R71") (pin "1") (pinfunction "1_1") (pintype "passive"))
      (node (ref "U14") (pin "2") (pinfunction "Vcc_2") (pintype "power_in"))
      (node (ref "U38") (pin "4") (pinfunction "VCC_4") (pintype "passive"))
    )
    (net (code "127") (name "unconnected-(D19-SCK-Pad3)") (class "Default")
      (node (ref "D19") (pin "3") (pinfunction "SCK_3") (pintype "passive"))
    )
    (net (code "128") (name "unconnected-(D20A-I{slash}O-Pad17)") (class "Default")
      (node (ref "D20") (pin "17") (pinfunction "I/O_17") (pintype "bidirectional"))
    )
    (net (code "129") (name "unconnected-(D20A-I{slash}O-Pad18)") (class "Default")
      (node (ref "D20") (pin "18") (pinfunction "I/O_18") (pintype "bidirectional"))
    )
    (net (code "130") (name "unconnected-(D20A-I{slash}O-Pad19)") (class "Default")
      (node (ref "D20") (pin "19") (pinfunction "I/O_19") (pintype "bidirectional"))
    )
    (net (code "131") (name "unconnected-(D20B-I{slash}O,_GSR-Pad31)") (class "Default")
      (node (ref "D20") (pin "31") (pinfunction "I/O,_GSR_31") (pintype "bidirectional"))
    )
    (net (code "132") (name "unconnected-(D20B-I{slash}O,_GTS2-Pad32)") (class "Default")
      (node (ref "D20") (pin "32") (pinfunction "I/O,_GTS2_32") (pintype "bidirectional"))
    )
    (net (code "133") (name "unconnected-(D20B-I{slash}O-Pad23)") (class "Default")
      (node (ref "D20") (pin "23") (pinfunction "I/O_23") (pintype "bidirectional"))
    )
    (net (code "134") (name "unconnected-(D20B-I{slash}O-Pad24)") (class "Default")
      (node (ref "D20") (pin "24") (pinfunction "I/O_24") (pintype "bidirectional"))
    )
    (net (code "135") (name "unconnected-(D20B-I{slash}O-Pad28)") (class "Default")
      (node (ref "D20") (pin "28") (pinfunction "I/O_28") (pintype "bidirectional"))
    )
    (net (code "136") (name "unconnected-(D20B-I{slash}O-Pad29)") (class "Default")
      (node (ref "D20") (pin "29") (pinfunction "I/O_29") (pintype "bidirectional"))
    )
    (net (code "137") (name "unconnected-(D20B-I{slash}O-Pad30)") (class "Default")
      (node (ref "D20") (pin "30") (pinfunction "I/O_30") (pintype "bidirectional"))
    )
    (net (code "138") (name "unconnected-(D20C-Input-Pad22)") (class "Default")
      (node (ref "D20") (pin "22") (pinfunction "Input_22") (pintype "input"))
    )
    (net (code "139") (name "unconnected-(D20F-Thermal_Pad-Pad33)") (class "Default")
      (node (ref "D20") (pin "33") (pinfunction "Thermal_Pad_33") (pintype "power_in"))
    )
    (net (code "140") (name "unconnected-(U14A-NC-Pad3)") (class "Default")
      (node (ref "U14") (pin "3") (pinfunction "NC_3") (pintype "input"))
    )
    (net (code "141") (name "unconnected-(U14A-NC_PDa0-Pad6)") (class "Default")
      (node (ref "U14") (pin "6") (pinfunction "NC_PDa0_6") (pintype "output"))
    )
    (net (code "142") (name "unconnected-(U14A-NC_PDa1-Pad5)") (class "Default")
      (node (ref "U14") (pin "5") (pinfunction "NC_PDa1_5") (pintype "output"))
    )
    (net (code "143") (name "unconnected-(U14A-NC_PDa2-Pad4)") (class "Default")
      (node (ref "U14") (pin "4") (pinfunction "NC_PDa2_4") (pintype "output"))
    )
    (net (code "144") (name "unconnected-(U14A-NC_PDa3-Pad11)") (class "Default")
      (node (ref "U14") (pin "11") (pinfunction "NC_PDa3_11") (pintype "output"))
    )
    (net (code "145") (name "unconnected-(U14A-NC_PDa4-Pad12)") (class "Default")
      (node (ref "U14") (pin "12") (pinfunction "NC_PDa4_12") (pintype "output"))
    )
    (net (code "146") (name "unconnected-(U14A-NC_PDa5-Pad13)") (class "Default")
      (node (ref "U14") (pin "13") (pinfunction "NC_PDa5_13") (pintype "output"))
    )
    (net (code "147") (name "unconnected-(U14A-NC_PDa6-Pad14)") (class "Default")
      (node (ref "U14") (pin "14") (pinfunction "NC_PDa6_14") (pintype "output"))
    )
    (net (code "148") (name "unconnected-(U22C-IO_L31N_GCLK30_D15_2-PadAB12)") (class "Default")
      (node (ref "U22") (pin "AB12") (pinfunction "IO_L31N_GCLK30_D15_2_AB12") (pintype "bidirectional"))
    )
    (net (code "149") (name "unconnected-(U22C-IO_L31P_GCLK31_D14_2-PadAA12)") (class "Default")
      (node (ref "U22") (pin "AA12") (pinfunction "IO_L31P_GCLK31_D14_2_AA12") (pintype "bidirectional"))
    )
    (net (code "150") (name "unconnected-(U38-TS-Pad1)") (class "Default")
      (node (ref "U38") (pin "1") (pinfunction "TS_1") (pintype "passive"))
    )
  )
)
